# RC522.net
KiCad netlist of a schematic drawn in Altium Designer
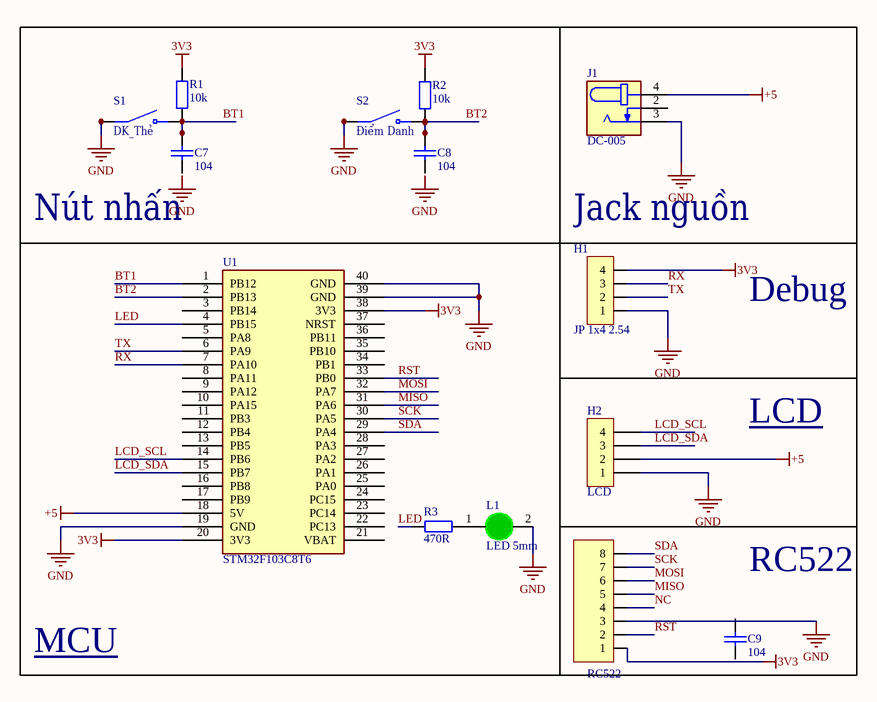
[diagram p0: RC522.SchDoc]

(export (version "E")
  (design (tool "Eeschema 10.0.6"))
  (components
    (comp (ref "C7")
      (value "104")
      (footprint "tu 1206")
      (description "Dán")
      (libsource (lib "Capacitor") (part "Tu 1206 104 50V 20%"))
    )
    (comp (ref "C8")
      (value "104")
      (footprint "tu 1206")
      (description "Dán")
      (libsource (lib "Capacitor") (part "Tu 1206 104 50V 20%"))
    )
    (comp (ref "C9")
      (value "104")
      (footprint "tu 1206")
      (description "Dán")
      (libsource (lib "Capacitor") (part "Tu 1206 104 50V 20%"))
    )
    (comp (ref "H1")
      (value "JP 1x4 2.54")
      (footprint "JP 1x4 DT")
      (description "Cắm")
      (libsource (lib "Jump") (part "JP 1x4 2.54 Duc Thang"))
    )
    (comp (ref "H2")
      (value "LCD")
      (footprint "XH2.54M-4")
      (description "Cắm")
      (libsource (lib "Header") (part "Header 4P 2.54 Duc Thang"))
    )
    (comp (ref "H3")
      (value "RC522")
      (footprint "JP 1x8 CT")
      (description "Cắm")
      (libsource (lib "Jump") (part "JP 1x8 2.54 Cai Thang"))
    )
    (comp (ref "J1")
      (value "DC-005")
      (footprint "NINIGI_DC-005")
      (description "DC Jack")
      (libsource (lib "DC-005") (part "DC-005"))
    )
    (comp (ref "L1")
      (value "LED 5mm")
      (footprint "LED-5MM-Green")
      (description "Cắm")
      (libsource (lib "Led") (part "LED 5mm Xanh La"))
    )
    (comp (ref "R1")
      (value "10k")
      (footprint "tro smd 1206")
      (description "Dán")
      (libsource (lib "Resistor") (part "Tro 1206 1% 10k"))
    )
    (comp (ref "R2")
      (value "10k")
      (footprint "tro smd 1206")
      (description "Dán")
      (libsource (lib "Resistor") (part "Tro 1206 1% 10k"))
    )
    (comp (ref "R3")
      (value "470R")
      (footprint "tro smd 1206")
      (description "Dán")
      (libsource (lib "Resistor") (part "Tro 1206 1% 1k"))
    )
    (comp (ref "S1")
      (value "DK_Thẻ")
      (footprint "SW_B3F-4055")
      (fields (field (name "MP") "B3F-4055"))
      (libsource (lib "B3F-4055") (part "B3F-4055"))
    )
    (comp (ref "S2")
      (value "Điểm Danh")
      (footprint "SW_B3F-4055")
      (fields (field (name "MP") "B3F-4055"))
      (libsource (lib "B3F-4055") (part "B3F-4055"))
    )
    (comp (ref "U1")
      (value "STM32F103C8T6")
      (footprint "Stm32 BluePill")
      (description "Designed By @Alixahedi")
      (libsource (lib "Stm32 Blue Pill") (part "BluePill"))
    )
  )
  (nets
    (net (code "1") (name "+5") (class "Default")
      (node (ref "H2") (pin "2") (pinfunction "2_2") (pintype "passive"))
      (node (ref "J1") (pin "4") (pinfunction "2_4") (pintype "passive"))
      (node (ref "U1") (pin "18") (pinfunction "5V_18") (pintype "passive"))
    )
    (net (code "2") (name "/BT1") (class "Default")
      (node (ref "C7") (pin "1") (pinfunction "1_1") (pintype "passive"))
      (node (ref "R1") (pin "1") (pinfunction "1_1") (pintype "passive"))
      (node (ref "S1") (pin "3") (pinfunction "NO_3") (pintype "passive"))
      (node (ref "S1") (pin "4") (pinfunction "NO_4") (pintype "passive"))
      (node (ref "U1") (pin "1") (pinfunction "PB12_1") (pintype "passive"))
    )
    (net (code "3") (name "/BT2") (class "Default")
      (node (ref "C8") (pin "1") (pinfunction "1_1") (pintype "passive"))
      (node (ref "R2") (pin "1") (pinfunction "1_1") (pintype "passive"))
      (node (ref "S2") (pin "3") (pinfunction "NO_3") (pintype "passive"))
      (node (ref "S2") (pin "4") (pinfunction "NO_4") (pintype "passive"))
      (node (ref "U1") (pin "2") (pinfunction "PB13_2") (pintype "passive"))
    )
    (net (code "4") (name "/LCD_SCL") (class "Default")
      (node (ref "H2") (pin "4") (pinfunction "4_4") (pintype "passive"))
      (node (ref "U1") (pin "14") (pinfunction "PB6_14") (pintype "passive"))
    )
    (net (code "5") (name "/LCD_SDA") (class "Default")
      (node (ref "H2") (pin "3") (pinfunction "3_3") (pintype "passive"))
      (node (ref "U1") (pin "15") (pinfunction "PB7_15") (pintype "passive"))
    )
    (net (code "6") (name "/LED") (class "Default")
      (node (ref "R3") (pin "2") (pinfunction "2_2") (pintype "passive"))
      (node (ref "U1") (pin "4") (pinfunction "PB15_4") (pintype "passive"))
    )
    (net (code "7") (name "/MISO") (class "Default")
      (node (ref "H3") (pin "5") (pinfunction "5_5") (pintype "passive"))
      (node (ref "U1") (pin "31") (pinfunction "PA6_31") (pintype "passive"))
    )
    (net (code "8") (name "/MOSI") (class "Default")
      (node (ref "H3") (pin "6") (pinfunction "6_6") (pintype "passive"))
      (node (ref "U1") (pin "32") (pinfunction "PA7_32") (pintype "passive"))
    )
    (net (code "9") (name "/NC") (class "Default")
      (node (ref "H3") (pin "4") (pinfunction "4_4") (pintype "passive"))
    )
    (net (code "10") (name "/RST") (class "Default")
      (node (ref "H3") (pin "2") (pinfunction "2_2") (pintype "passive"))
      (node (ref "U1") (pin "33") (pinfunction "PB0_33") (pintype "passive"))
    )
    (net (code "11") (name "/RX") (class "Default")
      (node (ref "H1") (pin "3") (pinfunction "3_3") (pintype "passive"))
      (node (ref "U1") (pin "7") (pinfunction "PA10_7") (pintype "passive"))
    )
    (net (code "12") (name "/SCK") (class "Default")
      (node (ref "H3") (pin "7") (pinfunction "7_7") (pintype "passive"))
      (node (ref "U1") (pin "30") (pinfunction "PA5_30") (pintype "passive"))
    )
    (net (code "13") (name "/SDA") (class "Default")
      (node (ref "H3") (pin "8") (pinfunction "8_8") (pintype "passive"))
      (node (ref "U1") (pin "29") (pinfunction "PA4_29") (pintype "passive"))
    )
    (net (code "14") (name "/TX") (class "Default")
      (node (ref "H1") (pin "2") (pinfunction "2_2") (pintype "passive"))
      (node (ref "U1") (pin "6") (pinfunction "PA9_6") (pintype "passive"))
    )
    (net (code "15") (name "3V3") (class "Default")
      (node (ref "H1") (pin "4") (pinfunction "4_4") (pintype "passive"))
      (node (ref "H3") (pin "1") (pinfunction "1_1") (pintype "passive"))
      (node (ref "R1") (pin "2") (pinfunction "2_2") (pintype "passive"))
      (node (ref "U1") (pin "20") (pinfunction "3V3_20") (pintype "passive"))
      (node (ref "U1") (pin "38") (pinfunction "3V3_38") (pintype "passive"))
    )
    (net (code "16") (name "GND") (class "Default")
      (node (ref "H1") (pin "1") (pinfunction "1_1") (pintype "passive"))
      (node (ref "H2") (pin "1") (pinfunction "1_1") (pintype "passive"))
      (node (ref "H3") (pin "3") (pinfunction "3_3") (pintype "passive"))
      (node (ref "J1") (pin "3") (pinfunction "5_3") (pintype "passive"))
      (node (ref "L1") (pin "2") (pinfunction "K_2") (pintype "passive"))
      (node (ref "S1") (pin "1") (pinfunction "COM_1") (pintype "passive"))
      (node (ref "S1") (pin "2") (pinfunction "COM_2") (pintype "passive"))
      (node (ref "S2") (pin "1") (pinfunction "COM_1") (pintype "passive"))
      (node (ref "S2") (pin "2") (pinfunction "COM_2") (pintype "passive"))
      (node (ref "U1") (pin "19") (pinfunction "GND_19") (pintype "passive"))
      (node (ref "U1") (pin "39") (pinfunction "GND_39") (pintype "passive"))
      (node (ref "U1") (pin "40") (pinfunction "GND_40") (pintype "passive"))
    )
    (net (code "17") (name "Net-(L1-A)") (class "Default")
      (node (ref "L1") (pin "1") (pinfunction "A_1") (pintype "passive"))
      (node (ref "R3") (pin "1") (pinfunction "1_1") (pintype "passive"))
    )
    (net (code "18") (name "unconnected-(C7-Pad2)") (class "Default")
      (node (ref "C7") (pin "2") (pinfunction "2_2") (pintype "passive"))
    )
    (net (code "19") (name "unconnected-(C8-Pad2)") (class "Default")
      (node (ref "C8") (pin "2") (pinfunction "2_2") (pintype "passive"))
    )
    (net (code "20") (name "unconnected-(C9-Pad1)") (class "Default")
      (node (ref "C9") (pin "1") (pinfunction "1_1") (pintype "passive"))
    )
    (net (code "21") (name "unconnected-(C9-Pad2)") (class "Default")
      (node (ref "C9") (pin "2") (pinfunction "2_2") (pintype "passive"))
    )
    (net (code "22") (name "unconnected-(J1-4-Pad2)") (class "Default")
      (node (ref "J1") (pin "2") (pinfunction "4_2") (pintype "passive"))
    )
    (net (code "23") (name "unconnected-(R2-Pad2)") (class "Default")
      (node (ref "R2") (pin "2") (pinfunction "2_2") (pintype "passive"))
    )
    (net (code "24") (name "unconnected-(U1-NRST-Pad37)") (class "Default")
      (node (ref "U1") (pin "37") (pinfunction "NRST_37") (pintype "passive"))
    )
    (net (code "25") (name "unconnected-(U1-PA0-Pad25)") (class "Default")
      (node (ref "U1") (pin "25") (pinfunction "PA0_25") (pintype "passive"))
    )
    (net (code "26") (name "unconnected-(U1-PA1-Pad26)") (class "Default")
      (node (ref "U1") (pin "26") (pinfunction "PA1_26") (pintype "passive"))
    )
    (net (code "27") (name "unconnected-(U1-PA2-Pad27)") (class "Default")
      (node (ref "U1") (pin "27") (pinfunction "PA2_27") (pintype "passive"))
    )
    (net (code "28") (name "unconnected-(U1-PA3-Pad28)") (class "Default")
      (node (ref "U1") (pin "28") (pinfunction "PA3_28") (pintype "passive"))
    )
    (net (code "29") (name "unconnected-(U1-PA8-Pad5)") (class "Default")
      (node (ref "U1") (pin "5") (pinfunction "PA8_5") (pintype "passive"))
    )
    (net (code "30") (name "unconnected-(U1-PA11-Pad8)") (class "Default")
      (node (ref "U1") (pin "8") (pinfunction "PA11_8") (pintype "passive"))
    )
    (net (code "31") (name "unconnected-(U1-PA12-Pad9)") (class "Default")
      (node (ref "U1") (pin "9") (pinfunction "PA12_9") (pintype "passive"))
    )
    (net (code "32") (name "unconnected-(U1-PA15-Pad10)") (class "Default")
      (node (ref "U1") (pin "10") (pinfunction "PA15_10") (pintype "passive"))
    )
    (net (code "33") (name "unconnected-(U1-PB1-Pad34)") (class "Default")
      (node (ref "U1") (pin "34") (pinfunction "PB1_34") (pintype "passive"))
    )
    (net (code "34") (name "unconnected-(U1-PB3-Pad11)") (class "Default")
      (node (ref "U1") (pin "11") (pinfunction "PB3_11") (pintype "passive"))
    )
    (net (code "35") (name "unconnected-(U1-PB4-Pad12)") (class "Default")
      (node (ref "U1") (pin "12") (pinfunction "PB4_12") (pintype "passive"))
    )
    (net (code "36") (name "unconnected-(U1-PB5-Pad13)") (class "Default")
      (node (ref "U1") (pin "13") (pinfunction "PB5_13") (pintype "passive"))
    )
    (net (code "37") (name "unconnected-(U1-PB8-Pad16)") (class "Default")
      (node (ref "U1") (pin "16") (pinfunction "PB8_16") (pintype "passive"))
    )
    (net (code "38") (name "unconnected-(U1-PB9-Pad17)") (class "Default")
      (node (ref "U1") (pin "17") (pinfunction "PB9_17") (pintype "passive"))
    )
    (net (code "39") (name "unconnected-(U1-PB10-Pad35)") (class "Default")
      (node (ref "U1") (pin "35") (pinfunction "PB10_35") (pintype "passive"))
    )
    (net (code "40") (name "unconnected-(U1-PB11-Pad36)") (class "Default")
      (node (ref "U1") (pin "36") (pinfunction "PB11_36") (pintype "passive"))
    )
    (net (code "41") (name "unconnected-(U1-PB14-Pad3)") (class "Default")
      (node (ref "U1") (pin "3") (pinfunction "PB14_3") (pintype "passive"))
    )
    (net (code "42") (name "unconnected-(U1-PC13-Pad22)") (class "Default")
      (node (ref "U1") (pin "22") (pinfunction "PC13_22") (pintype "passive"))
    )
    (net (code "43") (name "unconnected-(U1-PC14-Pad23)") (class "Default")
      (node (ref "U1") (pin "23") (pinfunction "PC14_23") (pintype "passive"))
    )
    (net (code "44") (name "unconnected-(U1-PC15-Pad24)") (class "Default")
      (node (ref "U1") (pin "24") (pinfunction "PC15_24") (pintype "passive"))
    )
    (net (code "45") (name "unconnected-(U1-VBAT-Pad21)") (class "Default")
      (node (ref "U1") (pin "21") (pinfunction "VBAT_21") (pintype "passive"))
    )
  )
)
